# USB_CP2104.net
KiCad netlist of a schematic drawn in Altium Designer
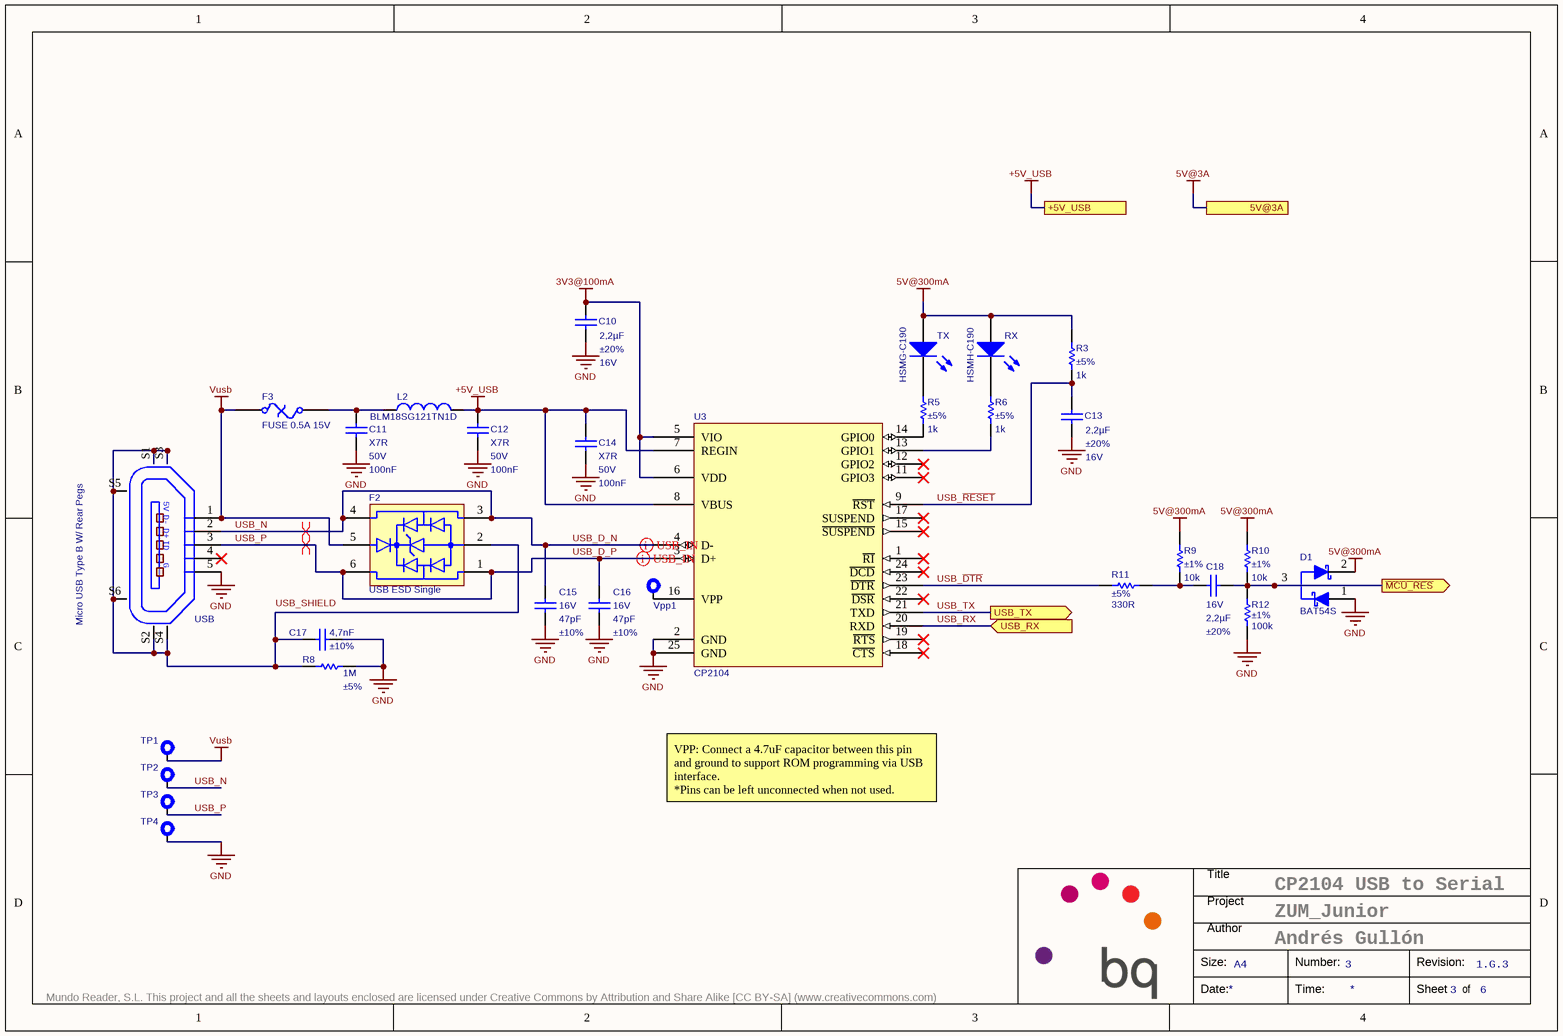
[diagram p0: USB_CP2104.SchDoc]

(export (version "E")
  (design (tool "Eeschema 10.0.6"))
  (components
    (comp (ref "C10")
      (value "C0402_2.2uF_16V_±20%")
      (footprint "C0402")
      (description "C0402_2.2uF_16V_±20%_X5R")
      (fields
        (field (name "VOLTAGE") "16V")
        (field (name "CAPACITANCE") "2,2µF")
        (field (name "PART NUMBER") "C0402_2.2uF_16V_±10%")
        (field (name "TOLERANCE") "±20%")
        (field (name "MANUFACTURER") "TDK")
      )
      (libsource (lib "BQ Vault") (part "Capacitor"))
    )
    (comp (ref "C11")
      (value "C0603_100nF_50V_±10%_X7R")
      (footprint "C0603")
      (fields
        (field (name "DIELECTRIC") "X7R")
        (field (name "VOLTAGE") "50V")
        (field (name "CAPACITANCE") "100nF")
        (field (name "MANUFACTURER") "Kemet")
        (field (name "TOLERANCE") "±10%")
      )
      (libsource (lib "BQ Vault") (part "CMP-00257-1"))
    )
    (comp (ref "C12")
      (value "C0603_100nF_50V_±10%_X7R")
      (footprint "C0603")
      (fields
        (field (name "DIELECTRIC") "X7R")
        (field (name "VOLTAGE") "50V")
        (field (name "CAPACITANCE") "100nF")
        (field (name "MANUFACTURER") "Kemet")
        (field (name "TOLERANCE") "±10%")
      )
      (libsource (lib "BQ Vault") (part "CMP-00257-1"))
    )
    (comp (ref "C13")
      (value "C0402_2.2uF_16V_±20%")
      (footprint "C0402")
      (description "C0402_2.2uF_16V_±20%_X5R")
      (fields
        (field (name "VOLTAGE") "16V")
        (field (name "CAPACITANCE") "2,2µF")
        (field (name "PART NUMBER") "C0402_2.2uF_16V_±10%")
        (field (name "TOLERANCE") "±20%")
        (field (name "MANUFACTURER") "TDK")
      )
      (libsource (lib "BQ Vault") (part "Capacitor"))
    )
    (comp (ref "C14")
      (value "C0603_100nF_50V_±10%_X7R")
      (footprint "C0603")
      (fields
        (field (name "DIELECTRIC") "X7R")
        (field (name "VOLTAGE") "50V")
        (field (name "CAPACITANCE") "100nF")
        (field (name "MANUFACTURER") "Kemet")
        (field (name "TOLERANCE") "±10%")
      )
      (libsource (lib "BQ Vault") (part "CMP-00257-1"))
    )
    (comp (ref "C15")
      (value "C0402_47pF_16V_±10%")
      (footprint "C0402")
      (fields
        (field (name "VOLTAGE") "16V")
        (field (name "CAPACITANCE") "47pF")
        (field (name "TOLERANCE") "±10%")
        (field (name "MANUFACTURER") "Kemet")
      )
      (libsource (lib "BQ Vault") (part "Capacitor"))
    )
    (comp (ref "C16")
      (value "C0402_47pF_16V_±10%")
      (footprint "C0402")
      (fields
        (field (name "VOLTAGE") "16V")
        (field (name "CAPACITANCE") "47pF")
        (field (name "TOLERANCE") "±10%")
        (field (name "MANUFACTURER") "Kemet")
      )
      (libsource (lib "BQ Vault") (part "Capacitor"))
    )
    (comp (ref "C17")
      (value "C0805_4700pF_250V_±10%_X7R")
      (footprint "C0805")
      (fields
        (field (name "VOLTAGE") "250V")
        (field (name "CAPACITANCE") "4,7nF")
        (field (name "PART NUMBER") "C0805_4700pF_250V_±10%")
        (field (name "TOLERANCE") "±10%")
        (field (name "MANUFACTURER") "TDK")
      )
      (libsource (lib "BQ Vault") (part "Capacitor"))
    )
    (comp (ref "C18")
      (value "C0402_2.2uF_16V_±20%")
      (footprint "C0402")
      (description "C0402_2.2uF_16V_±20%_X5R")
      (fields
        (field (name "VOLTAGE") "16V")
        (field (name "CAPACITANCE") "2,2µF")
        (field (name "PART NUMBER") "C0402_2.2uF_16V_±10%")
        (field (name "TOLERANCE") "±20%")
        (field (name "MANUFACTURER") "TDK")
      )
      (libsource (lib "BQ Vault") (part "Capacitor"))
    )
    (comp (ref "D1")
      (value "BAT54S")
      (footprint "SOT23-3")
      (description "Schottky Diode")
      (fields (field (name "MANUFACTURER") "NXP"))
      (libsource (lib "BQ Vault") (part "CMP-A2299-1"))
    )
    (comp (ref "F2")
      (value "USB ESD Single")
      (footprint "SOT563")
      (description "TVS Diode Array")
      (fields (field (name "MANUFACTURER") "Würth Elektronik"))
      (libsource (lib "BQ Vault") (part "ESDUSB"))
    )
    (comp (ref "F3")
      (value "FUSE 0.5A 15V")
      (footprint "F1812")
      (description "Resettable Fuses")
      (fields (field (name "VOLTAGE") "15V") (field (name "MANUFACTURER") "Bourns"))
      (libsource (lib "BQ Vault") (part "PTC_Fuse"))
    )
    (comp (ref "L2")
      (value "L0603_120R_0,025R_3000mA")
      (footprint "L0603")
      (fields (field (name "ORDERINGCODE") "BLM18SG121TN1D") (field (name "MANUFACTURER") "Murata"))
      (libsource (lib "BQ Vault") (part "Ferrite Bead"))
    )
    (comp (ref "R3")
      (value "R0402_1k_0.063W_±5%")
      (footprint "R0402")
      (fields
        (field (name "TOLERANCE") "±5%")
        (field (name "POWER") "0.063W")
        (field (name "RESISTANCE") "1k")
        (field (name "MANUFACTURER") "Vishay")
      )
      (libsource (lib "BQ Vault") (part "Resistor"))
    )
    (comp (ref "R5")
      (value "R0402_1k_0.063W_±5%")
      (footprint "R0402")
      (fields
        (field (name "TOLERANCE") "±5%")
        (field (name "POWER") "0.063W")
        (field (name "RESISTANCE") "1k")
        (field (name "MANUFACTURER") "Vishay")
      )
      (libsource (lib "BQ Vault") (part "Resistor"))
    )
    (comp (ref "R6")
      (value "R0402_1k_0.063W_±5%")
      (footprint "R0402")
      (fields
        (field (name "TOLERANCE") "±5%")
        (field (name "POWER") "0.063W")
        (field (name "RESISTANCE") "1k")
        (field (name "MANUFACTURER") "Vishay")
      )
      (libsource (lib "BQ Vault") (part "Resistor"))
    )
    (comp (ref "R8")
      (value "R0603_1M_0.1W_±5%")
      (footprint "R0603")
      (fields
        (field (name "TOLERANCE") "±5%")
        (field (name "POWER") "0.1W")
        (field (name "RESISTANCE") "1M")
        (field (name "MANUFACTURER") "Vishay")
      )
      (libsource (lib "BQ Vault") (part "Resistor"))
    )
    (comp (ref "R9")
      (value "R0402_10k_0.063W_±1%")
      (footprint "R0402")
      (fields
        (field (name "TOLERANCE") "±1%")
        (field (name "POWER") "0.063W")
        (field (name "RESISTANCE") "10k")
        (field (name "MANUFACTURER") "Vishay")
      )
      (libsource (lib "BQ Vault") (part "CMP-A1837-1"))
    )
    (comp (ref "R10")
      (value "R0402_10k_0.063W_±1%")
      (footprint "R0402")
      (fields
        (field (name "TOLERANCE") "±1%")
        (field (name "POWER") "0.063W")
        (field (name "RESISTANCE") "10k")
        (field (name "MANUFACTURER") "Vishay")
      )
      (libsource (lib "BQ Vault") (part "CMP-A1837-1"))
    )
    (comp (ref "R11")
      (value "R0402_330R_0.063W_±5%")
      (footprint "R0402")
      (fields
        (field (name "TOLERANCE") "±5%")
        (field (name "POWER") "0.063W")
        (field (name "RESISTANCE") "330R")
        (field (name "MANUFACTURER") "Vishay")
      )
      (libsource (lib "BQ Vault") (part "Resistor"))
    )
    (comp (ref "R12")
      (value "R0402_100k_0.063W_±1%")
      (footprint "R0402")
      (fields
        (field (name "TOLERANCE") "±1%")
        (field (name "POWER") "0.063W")
        (field (name "RESISTANCE") "100k")
        (field (name "MANUFACTURER") "Vishay")
      )
      (libsource (lib "BQ Vault") (part "CMP-A1835-2"))
    )
    (comp (ref "RX")
      (value "HSMH-C190")
      (footprint "LED0603")
      (description "LED")
      (fields (field (name "MANUFACTURER") "Avago Technologies"))
      (libsource (lib "BQ Vault") (part "LED"))
    )
    (comp (ref "TP1")
      (value "TP")
      (footprint "TP_POWER")
      (description "Testpoint 0.3mm")
      (fields (field (name "MANUFACTURER") "Oxley") (field (name "PART NUMBER") "TP_POWER"))
      (libsource (lib "BQ Vault") (part "CMP-A2499-3"))
    )
    (comp (ref "TP2")
      (value "TP_POWER")
      (footprint "TP_POWER")
      (description "Testpoint 0.3mm")
      (fields (field (name "MANUFACTURER") "Oxley"))
      (libsource (lib "BQ Vault") (part "CMP-A2499-3"))
    )
    (comp (ref "TP3")
      (value "TP_POWER")
      (footprint "TP_POWER")
      (description "Testpoint 0.3mm")
      (fields (field (name "MANUFACTURER") "Oxley"))
      (libsource (lib "BQ Vault") (part "CMP-A2499-3"))
    )
    (comp (ref "TP4")
      (value "TP_POWER")
      (footprint "TP_POWER")
      (description "Testpoint 0.3mm")
      (fields (field (name "MANUFACTURER") "Oxley"))
      (libsource (lib "BQ Vault") (part "CMP-A2499-3"))
    )
    (comp (ref "TX")
      (value "HSMG-C190")
      (footprint "LED0603")
      (description "LED")
      (fields (field (name "MANUFACTURER") "Avago Technologies"))
      (libsource (lib "BQ Vault") (part "LED"))
    )
    (comp (ref "U3")
      (value "CP2104")
      (footprint "QFN24_no_power")
      (description "USB to UART Bridge")
      (fields (field (name "MANUFACTURER") "Silicon Labs"))
      (libsource (lib "BQ Vault") (part "CP2104"))
    )
    (comp (ref "USB")
      (value "Micro USB Type B W/ Rear Pegs")
      (footprint "USB_B_W_REAR_PEGS")
      (fields (field (name "MANUFACTURER") "FCI"))
      (libsource (lib "BQ Vault") (part "USB_Micro_Type_B"))
    )
    (comp (ref "Vpp1")
      (value "TP_POWER")
      (footprint "TP_POWER")
      (description "Testpoint 0.3mm")
      (fields (field (name "MANUFACTURER") "Oxley"))
      (libsource (lib "BQ Vault") (part "CMP-A2499-3"))
    )
  )
  (nets
    (net (code "1") (name "+5V_USB") (class "Default")
      (node (ref "C12") (pin "2") (pinfunction "2_2") (pintype "passive"))
      (node (ref "C14") (pin "2") (pinfunction "2_2") (pintype "passive"))
      (node (ref "L2") (pin "2") (pinfunction "2_2") (pintype "passive"))
      (node (ref "U3") (pin "7") (pinfunction "REGIN_7") (pintype "power_in"))
      (node (ref "U3") (pin "8") (pinfunction "VBUS_8") (pintype "power_in"))
    )
    (net (code "2") (name "/USB_D_N") (class "Default")
      (node (ref "C15") (pin "2") (pinfunction "2_2") (pintype "passive"))
      (node (ref "F2") (pin "3") (pinfunction "3_3") (pintype "passive"))
      (node (ref "F2") (pin "4") (pinfunction "4_4") (pintype "passive"))
      (node (ref "TP2") (pin "1") (pinfunction "1_1") (pintype "passive"))
      (node (ref "U3") (pin "4") (pinfunction "D-_4") (pintype "bidirectional"))
      (node (ref "USB") (pin "2") (pinfunction "P2_2") (pintype "passive"))
    )
    (net (code "3") (name "/USB_D_P") (class "Default")
      (node (ref "C16") (pin "2") (pinfunction "2_2") (pintype "passive"))
      (node (ref "F2") (pin "1") (pinfunction "1_1") (pintype "passive"))
      (node (ref "F2") (pin "6") (pinfunction "6_6") (pintype "passive"))
      (node (ref "TP3") (pin "1") (pinfunction "1_1") (pintype "passive"))
      (node (ref "U3") (pin "3") (pinfunction "D+_3") (pintype "bidirectional"))
      (node (ref "USB") (pin "3") (pinfunction "P3_3") (pintype "passive"))
    )
    (net (code "4") (name "/USB_RX") (class "Default")
      (node (ref "U3") (pin "20") (pinfunction "RXD_20") (pintype "input"))
    )
    (net (code "6") (name "/USB_TX") (class "Default")
      (node (ref "U3") (pin "21") (pinfunction "TXD_21") (pintype "output"))
    )
    (net (code "7") (name "/USB_~{DTR}") (class "Default")
      (node (ref "R11") (pin "1") (pinfunction "1_1") (pintype "passive"))
      (node (ref "U3") (pin "23") (pinfunction "~{DTR}_23") (pintype "output"))
    )
    (net (code "8") (name "/USB_~{RESET}") (class "Default")
      (node (ref "C13") (pin "2") (pinfunction "2_2") (pintype "passive"))
      (node (ref "R3") (pin "1") (pinfunction "1_1") (pintype "passive"))
      (node (ref "U3") (pin "9") (pinfunction "~{RST}_9") (pintype "input"))
    )
    (net (code "9") (name "/~{MCU_RES}") (class "Default")
      (node (ref "C18") (pin "1") (pinfunction "1_1") (pintype "passive"))
      (node (ref "D1") (pin "3") (pinfunction "K1_3") (pintype "passive"))
      (node (ref "R10") (pin "2") (pinfunction "2_2") (pintype "passive"))
      (node (ref "R12") (pin "1") (pinfunction "1_1") (pintype "passive"))
    )
    (net (code "10") (name "3V3@100mA") (class "Default")
      (node (ref "C10") (pin "2") (pinfunction "2_2") (pintype "passive"))
      (node (ref "U3") (pin "5") (pinfunction "VIO_5") (pintype "power_in"))
      (node (ref "U3") (pin "6") (pinfunction "VDD_6") (pintype "power_in"))
    )
    (net (code "12") (name "5V@300mA") (class "Default")
      (node (ref "D1") (pin "2") (pinfunction "K2_2") (pintype "passive"))
      (node (ref "R10") (pin "1") (pinfunction "1_1") (pintype "passive"))
      (node (ref "R3") (pin "2") (pinfunction "2_2") (pintype "passive"))
      (node (ref "R9") (pin "1") (pinfunction "1_1") (pintype "passive"))
      (node (ref "RX") (pin "A") (pinfunction "A_A") (pintype "passive"))
      (node (ref "TX") (pin "A") (pinfunction "A_A") (pintype "passive"))
    )
    (net (code "13") (name "GND") (class "Default")
      (node (ref "C10") (pin "1") (pinfunction "1_1") (pintype "passive"))
      (node (ref "C11") (pin "1") (pinfunction "1_1") (pintype "passive"))
      (node (ref "C12") (pin "1") (pinfunction "1_1") (pintype "passive"))
      (node (ref "C13") (pin "1") (pinfunction "1_1") (pintype "passive"))
      (node (ref "C14") (pin "1") (pinfunction "1_1") (pintype "passive"))
      (node (ref "C15") (pin "1") (pinfunction "1_1") (pintype "passive"))
      (node (ref "C16") (pin "1") (pinfunction "1_1") (pintype "passive"))
      (node (ref "C17") (pin "2") (pinfunction "2_2") (pintype "passive"))
      (node (ref "D1") (pin "1") (pinfunction "A_1") (pintype "passive"))
      (node (ref "R12") (pin "2") (pinfunction "2_2") (pintype "passive"))
      (node (ref "R8") (pin "1") (pinfunction "1_1") (pintype "passive"))
      (node (ref "TP4") (pin "1") (pinfunction "1_1") (pintype "passive"))
      (node (ref "U3") (pin "2") (pinfunction "GND_2") (pintype "power_in"))
      (node (ref "U3") (pin "25") (pinfunction "GND_25") (pintype "power_in"))
      (node (ref "USB") (pin "5") (pinfunction "P5_5") (pintype "passive"))
    )
    (net (code "14") (name "Net-(C11-Pad2)") (class "Default")
      (node (ref "C11") (pin "2") (pinfunction "2_2") (pintype "passive"))
      (node (ref "F3") (pin "2") (pinfunction "2_2") (pintype "passive"))
      (node (ref "L2") (pin "1") (pinfunction "1_1") (pintype "passive"))
    )
    (net (code "15") (name "Net-(C18-Pad2)") (class "Default")
      (node (ref "C18") (pin "2") (pinfunction "2_2") (pintype "passive"))
      (node (ref "R11") (pin "2") (pinfunction "2_2") (pintype "passive"))
      (node (ref "R9") (pin "2") (pinfunction "2_2") (pintype "passive"))
    )
    (net (code "16") (name "Net-(R5-Pad2)") (class "Default")
      (node (ref "R5") (pin "2") (pinfunction "2_2") (pintype "passive"))
      (node (ref "TX") (pin "K") (pinfunction "K_K") (pintype "passive"))
    )
    (net (code "17") (name "Net-(R6-Pad2)") (class "Default")
      (node (ref "R6") (pin "2") (pinfunction "2_2") (pintype "passive"))
      (node (ref "RX") (pin "K") (pinfunction "K_K") (pintype "passive"))
    )
    (net (code "18") (name "Net-(U3-GPIO0)") (class "Default")
      (node (ref "R5") (pin "1") (pinfunction "1_1") (pintype "passive"))
      (node (ref "U3") (pin "14") (pinfunction "GPIO0_14") (pintype "bidirectional"))
    )
    (net (code "19") (name "Net-(U3-GPIO1)") (class "Default")
      (node (ref "R6") (pin "1") (pinfunction "1_1") (pintype "passive"))
      (node (ref "U3") (pin "13") (pinfunction "GPIO1_13") (pintype "bidirectional"))
    )
    (net (code "20") (name "Net-(U3-VPP)") (class "Default")
      (node (ref "U3") (pin "16") (pinfunction "VPP_16") (pintype "power_in"))
      (node (ref "Vpp1") (pin "1") (pinfunction "1_1") (pintype "passive"))
    )
    (net (code "21") (name "Net-(USB-SHLD1)") (class "Default")
      (node (ref "C17") (pin "1") (pinfunction "1_1") (pintype "passive"))
      (node (ref "F2") (pin "2") (pinfunction "2_2") (pintype "passive"))
      (node (ref "R8") (pin "2") (pinfunction "2_2") (pintype "passive"))
      (node (ref "USB") (pin "S1") (pinfunction "SHLD1_S1") (pintype "passive"))
      (node (ref "USB") (pin "S2") (pinfunction "SHLD2_S2") (pintype "passive"))
      (node (ref "USB") (pin "S3") (pinfunction "SHLD3_S3") (pintype "passive"))
      (node (ref "USB") (pin "S4") (pinfunction "SHLD4_S4") (pintype "passive"))
      (node (ref "USB") (pin "S5") (pinfunction "SHLD5_S5") (pintype "passive"))
      (node (ref "USB") (pin "S6") (pinfunction "SHLD6_S6") (pintype "passive"))
    )
    (net (code "22") (name "Vusb") (class "Default")
      (node (ref "F2") (pin "5") (pinfunction "5_5") (pintype "passive"))
      (node (ref "F3") (pin "1") (pinfunction "1_1") (pintype "passive"))
      (node (ref "TP1") (pin "1") (pinfunction "1_1") (pintype "passive"))
      (node (ref "USB") (pin "1") (pinfunction "P1_1") (pintype "passive"))
    )
    (net (code "23") (name "unconnected-(U3-GPIO2-Pad12)") (class "Default")
      (node (ref "U3") (pin "12") (pinfunction "GPIO2_12") (pintype "bidirectional+no_connect"))
    )
    (net (code "24") (name "unconnected-(U3-GPIO3-Pad11)") (class "Default")
      (node (ref "U3") (pin "11") (pinfunction "GPIO3_11") (pintype "bidirectional+no_connect"))
    )
    (net (code "25") (name "unconnected-(U3-SUSPEND-Pad17)") (class "Default")
      (node (ref "U3") (pin "17") (pinfunction "SUSPEND_17") (pintype "output+no_connect"))
    )
    (net (code "26") (name "unconnected-(U3-~{CTS}-Pad18)") (class "Default")
      (node (ref "U3") (pin "18") (pinfunction "~{CTS}_18") (pintype "input+no_connect"))
    )
    (net (code "27") (name "unconnected-(U3-~{DCD}-Pad24)") (class "Default")
      (node (ref "U3") (pin "24") (pinfunction "~{DCD}_24") (pintype "input+no_connect"))
    )
    (net (code "28") (name "unconnected-(U3-~{DSR}-Pad22)") (class "Default")
      (node (ref "U3") (pin "22") (pinfunction "~{DSR}_22") (pintype "input+no_connect"))
    )
    (net (code "29") (name "unconnected-(U3-~{RI}-Pad1)") (class "Default")
      (node (ref "U3") (pin "1") (pinfunction "~{RI}_1") (pintype "input+no_connect"))
    )
    (net (code "30") (name "unconnected-(U3-~{RTS}-Pad19)") (class "Default")
      (node (ref "U3") (pin "19") (pinfunction "~{RTS}_19") (pintype "output+no_connect"))
    )
    (net (code "31") (name "unconnected-(U3-~{SUSPEND}-Pad15)") (class "Default")
      (node (ref "U3") (pin "15") (pinfunction "~{SUSPEND}_15") (pintype "output+no_connect"))
    )
    (net (code "32") (name "unconnected-(USB-P4-Pad4)") (class "Default")
      (node (ref "USB") (pin "4") (pinfunction "P4_4") (pintype "passive+no_connect"))
    )
  )
)
